# HEL-IOT-0_4.net
KiCad netlist of a schematic drawn in EAGLE
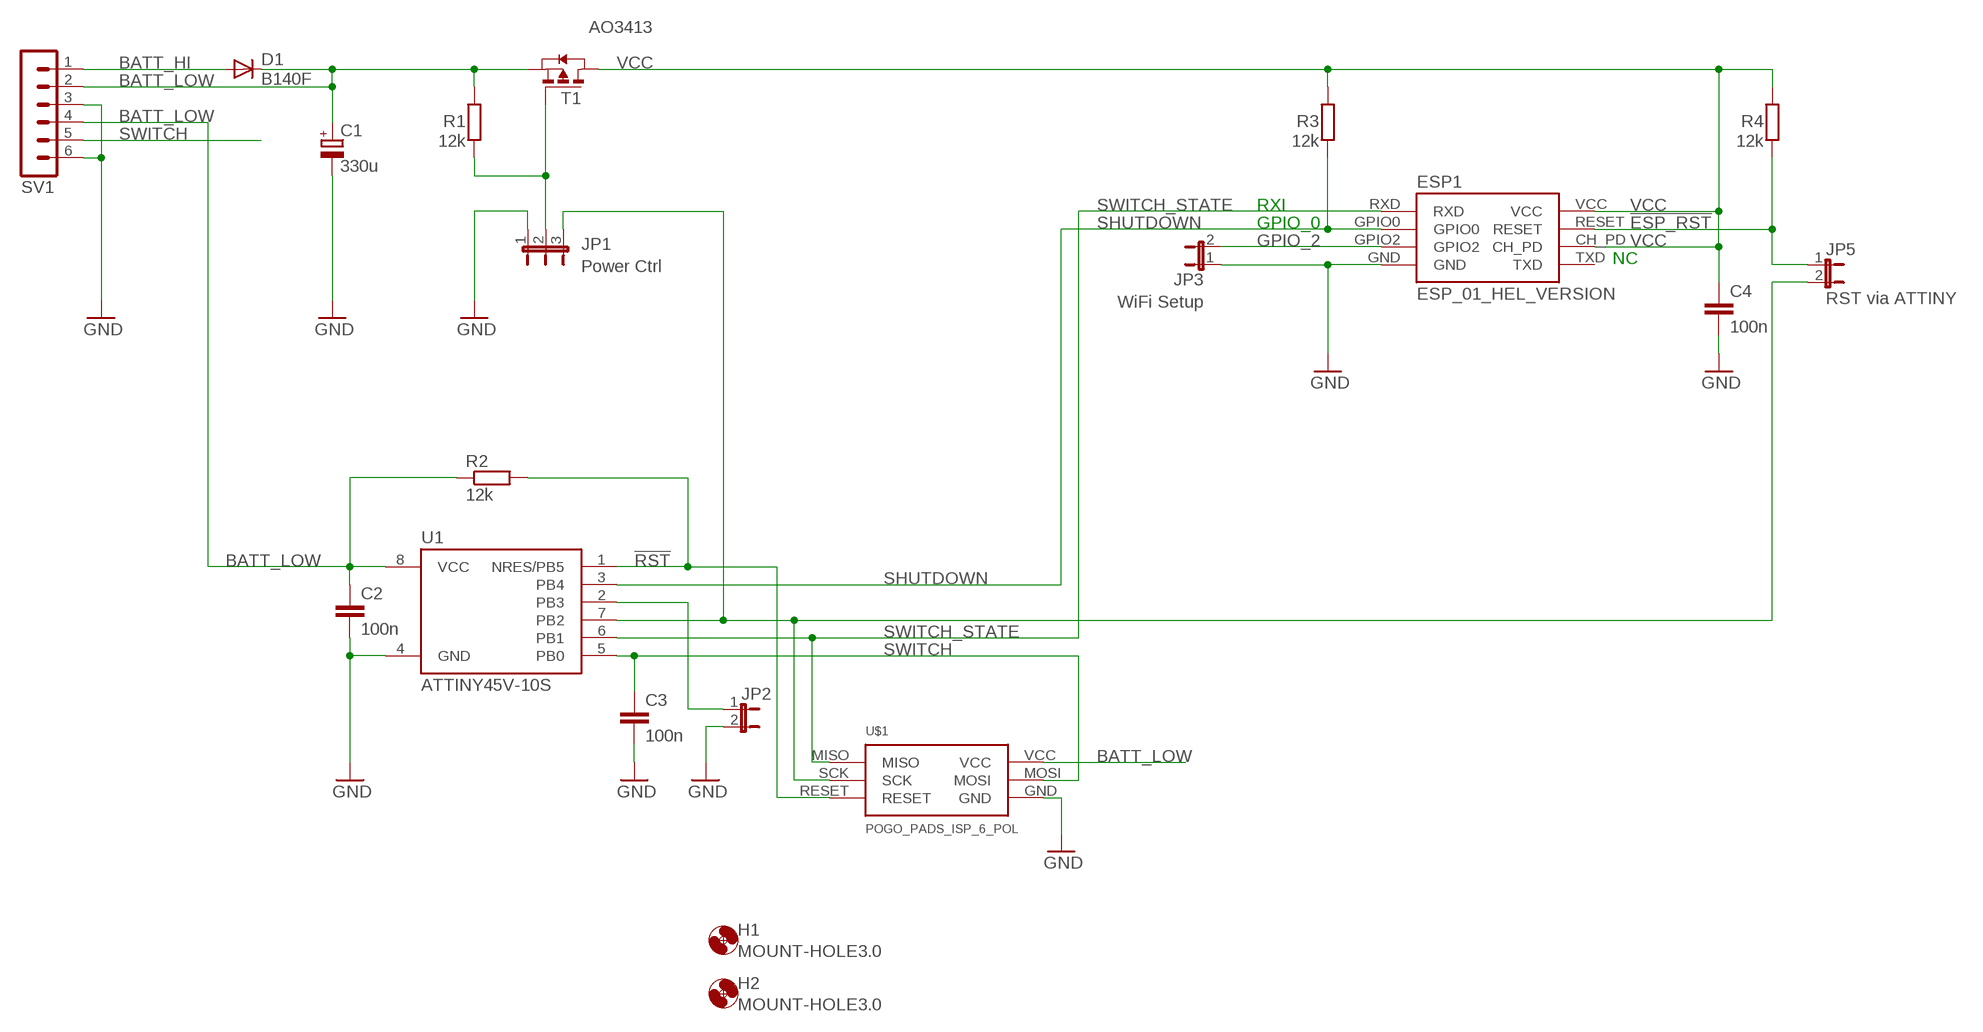
[diagram p0: schematic, sheet 1]

(export (version "E")
  (design (tool "Eeschema 10.0.6"))
  (components
    (comp (ref "C1")
      (value "330u")
      (footprint "eagle-import:UD-8X10_NICHICON")
      (libsource (lib "eagle-import") (part "CPOL-EUUD-8X10"))
    )
    (comp (ref "C2")
      (value "100n")
      (footprint "eagle-import:C3225")
      (libsource (lib "eagle-import") (part "C-EUC3225"))
    )
    (comp (ref "C3")
      (value "100n")
      (footprint "eagle-import:C3225")
      (libsource (lib "eagle-import") (part "C-EUC3225"))
    )
    (comp (ref "C4")
      (value "100n")
      (footprint "eagle-import:C3225")
      (libsource (lib "eagle-import") (part "C-EUC3225"))
    )
    (comp (ref "D1")
      (value "B140F")
      (footprint "eagle-import:DO214AA")
      (libsource (lib "eagle-import") (part "DIODE-DO214AA"))
    )
    (comp (ref "ESP1")
      (value "ESP_01_HEL_VERSION")
      (footprint "eagle-import:CUSTOM_ESP01_FOR_HEL")
      (libsource (lib "eagle-import") (part "ESP_01_HEL_VERSION"))
    )
    (comp (ref "H1")
      (value "MOUNT-HOLE3.0")
      (footprint "eagle-import:3,0")
      (libsource (lib "eagle-import") (part "MOUNT-HOLE3.0"))
    )
    (comp (ref "H2")
      (value "MOUNT-HOLE3.0")
      (footprint "eagle-import:3,0")
      (libsource (lib "eagle-import") (part "MOUNT-HOLE3.0"))
    )
    (comp (ref "JP1")
      (value "Power Ctrl")
      (footprint "eagle-import:JP2")
      (libsource (lib "eagle-import") (part "JP2E"))
    )
    (comp (ref "JP2")
      (value "JP1E")
      (footprint "eagle-import:JP1")
      (libsource (lib "eagle-import") (part "JP1E"))
    )
    (comp (ref "JP3")
      (value "WiFi Setup")
      (footprint "eagle-import:JP1")
      (libsource (lib "eagle-import") (part "JP1E"))
    )
    (comp (ref "JP5")
      (value "RST via ATTINY")
      (footprint "eagle-import:JP1")
      (libsource (lib "eagle-import") (part "JP1E"))
    )
    (comp (ref "R1")
      (value "12k")
      (footprint "eagle-import:R0805")
      (libsource (lib "eagle-import") (part "R-EU_R0805"))
    )
    (comp (ref "R2")
      (value "12k")
      (footprint "eagle-import:R0805")
      (libsource (lib "eagle-import") (part "R-EU_R0805"))
    )
    (comp (ref "R3")
      (value "12k")
      (footprint "eagle-import:R0805")
      (libsource (lib "eagle-import") (part "R-EU_R0805"))
    )
    (comp (ref "R4")
      (value "12k")
      (footprint "eagle-import:R0805")
      (libsource (lib "eagle-import") (part "R-EU_R0805"))
    )
    (comp (ref "SV1")
      (value "MA06-1")
      (footprint "eagle-import:MA06-1")
      (libsource (lib "eagle-import") (part "MA06-1"))
    )
    (comp (ref "T1")
      (value "AO3413")
      (footprint "eagle-import:SOT-23")
      (libsource (lib "eagle-import") (part "PMOSSOT23"))
    )
    (comp (ref "U$1")
      (value "POGO_PADS_ISP_6_POL")
      (footprint "eagle-import:POGO_PADS_ISP_6_POL")
      (libsource (lib "eagle-import") (part "POGO_PADS_ISP_6_POL"))
    )
    (comp (ref "U1")
      (value "ATTINY45V-10S")
      (footprint "eagle-import:SOIC8_EIAJ_208MIL")
      (libsource (lib "eagle-import") (part "ATTINY45SV-10"))
    )
  )
  (nets
    (net (code "1") (name "/BATT_HI") (class "Default")
      (node (ref "D1") (pin "A") (pinfunction "A_A") (pintype "passive"))
      (node (ref "SV1") (pin "1") (pinfunction "1_1") (pintype "passive"))
    )
    (net (code "2") (name "/BATT_LOW") (class "Default")
      (node (ref "C1") (pin "+") (pinfunction "+_+") (pintype "passive"))
      (node (ref "C2") (pin "1") (pinfunction "1_1") (pintype "passive"))
      (node (ref "D1") (pin "C") (pinfunction "C_C") (pintype "passive"))
      (node (ref "R1") (pin "2") (pinfunction "2_2") (pintype "passive"))
      (node (ref "R2") (pin "1") (pinfunction "1_1") (pintype "passive"))
      (node (ref "SV1") (pin "2") (pinfunction "2_2") (pintype "passive"))
      (node (ref "SV1") (pin "4") (pinfunction "4_4") (pintype "passive"))
      (node (ref "T1") (pin "2") (pinfunction "S_2") (pintype "passive"))
      (node (ref "U$1") (pin "VCC") (pinfunction "VCC_VCC") (pintype "bidirectional"))
      (node (ref "U1") (pin "8") (pinfunction "VCC_8") (pintype "power_in"))
    )
    (net (code "3") (name "/GPIO_2") (class "Default")
      (node (ref "ESP1") (pin "GPIO2") (pinfunction "GPIO2_GPIO2") (pintype "bidirectional"))
      (node (ref "JP3") (pin "2") (pinfunction "2_2") (pintype "passive"))
    )
    (net (code "4") (name "/SHUTDOWN") (class "Default")
      (node (ref "ESP1") (pin "GPIO0") (pinfunction "GPIO0_GPIO0") (pintype "bidirectional"))
      (node (ref "R3") (pin "1") (pinfunction "1_1") (pintype "passive"))
      (node (ref "U1") (pin "3") (pinfunction "PB4_3") (pintype "bidirectional"))
    )
    (net (code "5") (name "/SWITCH") (class "Default")
      (node (ref "C3") (pin "1") (pinfunction "1_1") (pintype "passive"))
      (node (ref "SV1") (pin "5") (pinfunction "5_5") (pintype "passive"))
      (node (ref "U$1") (pin "MOSI") (pinfunction "MOSI_MOSI") (pintype "bidirectional"))
      (node (ref "U1") (pin "5") (pinfunction "PB0_5") (pintype "bidirectional"))
    )
    (net (code "6") (name "/SWITCH_STATE") (class "Default")
      (node (ref "ESP1") (pin "RXD") (pinfunction "RXD_RXD") (pintype "bidirectional"))
      (node (ref "U$1") (pin "MISO") (pinfunction "MISO_MISO") (pintype "bidirectional"))
      (node (ref "U1") (pin "6") (pinfunction "PB1_6") (pintype "bidirectional"))
    )
    (net (code "7") (name "/VCC") (class "Default")
      (node (ref "C4") (pin "1") (pinfunction "1_1") (pintype "passive"))
      (node (ref "ESP1") (pin "CH_PD") (pinfunction "CH_PD_CH_PD") (pintype "bidirectional"))
      (node (ref "ESP1") (pin "VCC") (pinfunction "VCC_VCC") (pintype "bidirectional"))
      (node (ref "R3") (pin "2") (pinfunction "2_2") (pintype "passive"))
      (node (ref "R4") (pin "2") (pinfunction "2_2") (pintype "passive"))
      (node (ref "T1") (pin "1") (pinfunction "D_1") (pintype "passive"))
    )
    (net (code "8") (name "/~{ESP_RST}") (class "Default")
      (node (ref "ESP1") (pin "RESET") (pinfunction "RESET_RESET") (pintype "bidirectional"))
      (node (ref "JP5") (pin "1") (pinfunction "1_1") (pintype "passive"))
      (node (ref "R4") (pin "1") (pinfunction "1_1") (pintype "passive"))
    )
    (net (code "9") (name "/~{RST}") (class "Default")
      (node (ref "R2") (pin "2") (pinfunction "2_2") (pintype "passive"))
      (node (ref "U$1") (pin "RESET") (pinfunction "RESET_RESET") (pintype "bidirectional"))
      (node (ref "U1") (pin "1") (pinfunction "NRES/PB5_1") (pintype "bidirectional"))
    )
    (net (code "10") (name "GND") (class "Default")
      (node (ref "C1") (pin "-") (pinfunction "-_-") (pintype "passive"))
      (node (ref "C2") (pin "2") (pinfunction "2_2") (pintype "passive"))
      (node (ref "C3") (pin "2") (pinfunction "2_2") (pintype "passive"))
      (node (ref "C4") (pin "2") (pinfunction "2_2") (pintype "passive"))
      (node (ref "ESP1") (pin "GND") (pinfunction "GND_GND") (pintype "bidirectional"))
      (node (ref "JP1") (pin "1") (pinfunction "1_1") (pintype "passive"))
      (node (ref "JP2") (pin "2") (pinfunction "2_2") (pintype "passive"))
      (node (ref "JP3") (pin "1") (pinfunction "1_1") (pintype "passive"))
      (node (ref "SV1") (pin "3") (pinfunction "3_3") (pintype "passive"))
      (node (ref "SV1") (pin "6") (pinfunction "6_6") (pintype "passive"))
      (node (ref "U$1") (pin "GND") (pinfunction "GND_GND") (pintype "bidirectional"))
      (node (ref "U1") (pin "4") (pinfunction "GND_4") (pintype "power_in"))
    )
    (net (code "11") (name "Net-(T1-G)") (class "Default")
      (node (ref "JP1") (pin "2") (pinfunction "2_2") (pintype "passive"))
      (node (ref "R1") (pin "1") (pinfunction "1_1") (pintype "passive"))
      (node (ref "T1") (pin "3") (pinfunction "G_3") (pintype "passive"))
    )
    (net (code "12") (name "Net-(U1-PB2)") (class "Default")
      (node (ref "JP1") (pin "3") (pinfunction "3_3") (pintype "passive"))
      (node (ref "JP5") (pin "2") (pinfunction "2_2") (pintype "passive"))
      (node (ref "U$1") (pin "SCK") (pinfunction "SCK_SCK") (pintype "bidirectional"))
      (node (ref "U1") (pin "7") (pinfunction "PB2_7") (pintype "bidirectional"))
    )
    (net (code "13") (name "Net-(U1-PB3)") (class "Default")
      (node (ref "JP2") (pin "1") (pinfunction "1_1") (pintype "passive"))
      (node (ref "U1") (pin "2") (pinfunction "PB3_2") (pintype "bidirectional"))
    )
    (net (code "14") (name "unconnected-(ESP1-PadTXD)") (class "Default")
      (node (ref "ESP1") (pin "TXD") (pinfunction "TXD_TXD") (pintype "bidirectional"))
    )
  )
)
